# EMI_Probe.net
KiCad netlist of a schematic drawn in Altium Designer
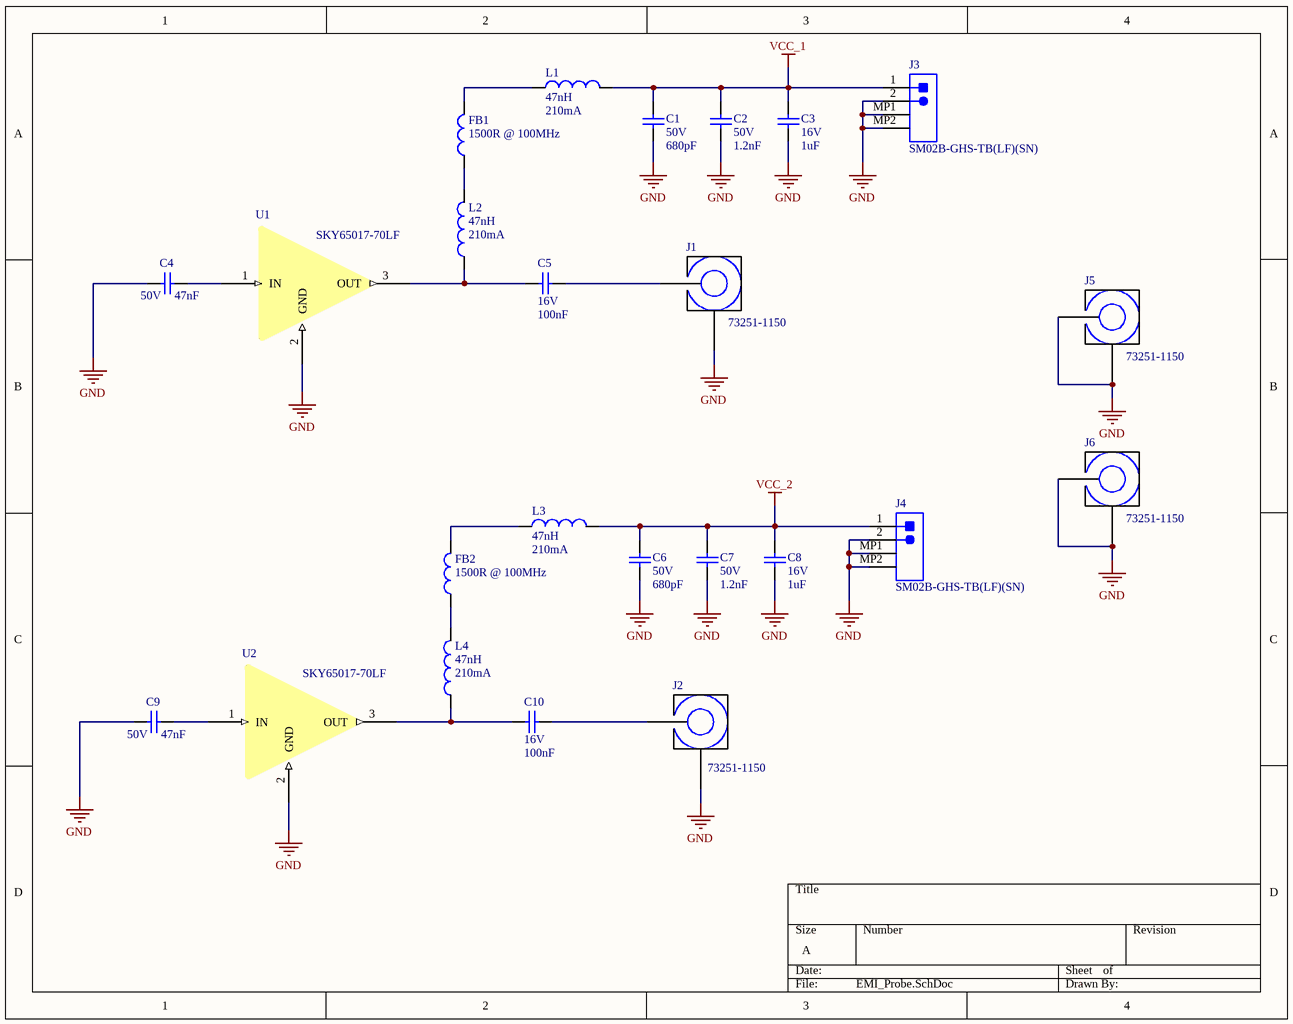
[diagram p0: EMI_Probe.SchDoc]

(export (version "E")
  (design (tool "Eeschema 10.0.6"))
  (components
    (comp (ref "C1")
      (value "680pF")
      (footprint "C0402[1005]")
      (description "680pF 50V X7R 10% 0402")
      (fields
        (field (name "MANUFACTURER") "Yageo")
        (field (name "MANUFACTURER PART NUMBER") "CC0402KRX7R9BB681")
        (field (name "VOLTAGE") "50V")
      )
      (libsource (lib "Kickmaker Library") (part "C680pF 50V 0402"))
    )
    (comp (ref "C2")
      (value "1.2nF")
      (footprint "C0603[1608]")
      (description "1.2nF 50V C0G,NP0 5% 0603")
      (fields
        (field (name "MANUFACTURER") "Walsin")
        (field (name "MANUFACTURER PART NUMBER") "0603N122J500CT")
        (field (name "VOLTAGE") "50V")
      )
      (libsource (lib "Kickmaker Library") (part "C1.2nF 50V 0603"))
    )
    (comp (ref "C3")
      (value "1uF")
      (footprint "C0402[1005]")
      (description "1uF 16V X5R 10% 0402")
      (fields
        (field (name "MANUFACTURER") "Samsung Electro-Mechanics")
        (field (name "MANUFACTURER PART NUMBER") "CL05A105KO5NNNC")
        (field (name "VOLTAGE") "16V")
      )
      (libsource (lib "Kickmaker Library") (part "C1uF 16V 0402"))
    )
    (comp (ref "C4")
      (value "47nF")
      (footprint "C0402[1005]")
      (description "47nF 50V X7R 10% 0402")
      (fields
        (field (name "MANUFACTURER") "Yageo")
        (field (name "MANUFACTURER PART NUMBER") "CC0402KRX7R9BB473")
        (field (name "VOLTAGE") "50V")
      )
      (libsource (lib "Kickmaker Library") (part "C47nF 50V 0402"))
    )
    (comp (ref "C5")
      (value "100nF")
      (footprint "C0402[1005]")
      (description "100nF 16V X7R 10% 0402")
      (fields
        (field (name "MANUFACTURER") "Kemet")
        (field (name "MANUFACTURER PART NUMBER") "C0402C104K4RACTU")
        (field (name "VOLTAGE") "16V")
      )
      (libsource (lib "Kickmaker Library") (part "C100nF 16V 0402"))
    )
    (comp (ref "C6")
      (value "680pF")
      (footprint "C0402[1005]")
      (description "680pF 50V X7R 10% 0402")
      (fields
        (field (name "MANUFACTURER") "Yageo")
        (field (name "MANUFACTURER PART NUMBER") "CC0402KRX7R9BB681")
        (field (name "VOLTAGE") "50V")
      )
      (libsource (lib "Kickmaker Library") (part "C680pF 50V 0402"))
    )
    (comp (ref "C7")
      (value "1.2nF")
      (footprint "C0603[1608]")
      (description "1.2nF 50V C0G,NP0 5% 0603")
      (fields
        (field (name "MANUFACTURER") "Walsin")
        (field (name "MANUFACTURER PART NUMBER") "0603N122J500CT")
        (field (name "VOLTAGE") "50V")
      )
      (libsource (lib "Kickmaker Library") (part "C1.2nF 50V 0603"))
    )
    (comp (ref "C8")
      (value "1uF")
      (footprint "C0402[1005]")
      (description "1uF 16V X5R 10% 0402")
      (fields
        (field (name "MANUFACTURER") "Samsung Electro-Mechanics")
        (field (name "MANUFACTURER PART NUMBER") "CL05A105KO5NNNC")
        (field (name "VOLTAGE") "16V")
      )
      (libsource (lib "Kickmaker Library") (part "C1uF 16V 0402"))
    )
    (comp (ref "C9")
      (value "47nF")
      (footprint "C0402[1005]")
      (description "47nF 50V X7R 10% 0402")
      (fields
        (field (name "MANUFACTURER") "Yageo")
        (field (name "MANUFACTURER PART NUMBER") "CC0402KRX7R9BB473")
        (field (name "VOLTAGE") "50V")
      )
      (libsource (lib "Kickmaker Library") (part "C47nF 50V 0402"))
    )
    (comp (ref "C10")
      (value "100nF")
      (footprint "C0402[1005]")
      (description "100nF 16V X7R 10% 0402")
      (fields
        (field (name "MANUFACTURER") "Kemet")
        (field (name "MANUFACTURER PART NUMBER") "C0402C104K4RACTU")
        (field (name "VOLTAGE") "16V")
      )
      (libsource (lib "Kickmaker Library") (part "C100nF 16V 0402"))
    )
    (comp (ref "FB1")
      (value "1500R @ 100MHz")
      (footprint "R0805[2012]")
      (description "1,5 kOhms @ 100MHz 1 Ligne de signal Ferrite Bead 0805 (2012 métrique) 1A 300mOhms")
      (fields
        (field (name "MANUFACTURER") "Wurth Electronics Inc.")
        (field (name "MANUFACTURER PART NUMBER") "742792097")
      )
      (libsource (lib "Kickmaker Library") (part "Ferrite bead 1.5 KOHM 0805 1LN"))
    )
    (comp (ref "FB2")
      (value "1500R @ 100MHz")
      (footprint "R0805[2012]")
      (description "1,5 kOhms @ 100MHz 1 Ligne de signal Ferrite Bead 0805 (2012 métrique) 1A 300mOhms")
      (fields
        (field (name "MANUFACTURER") "Wurth Electronics Inc.")
        (field (name "MANUFACTURER PART NUMBER") "742792097")
      )
      (libsource (lib "Kickmaker Library") (part "Ferrite bead 1.5 KOHM 0805 1LN"))
    )
    (comp (ref "J1")
      (value "73251-1150")
      (footprint "732511040")
      (fields (field (name "MANUFACTURER") "Molex"))
      (libsource (lib "Connector") (part "SMA RA 50ohm"))
    )
    (comp (ref "J2")
      (value "73251-1150")
      (footprint "732511040")
      (fields (field (name "MANUFACTURER") "Molex"))
      (libsource (lib "Connector") (part "SMA RA 50ohm"))
    )
    (comp (ref "J3")
      (value "SM02B-GHS-TB(LF)(SN)")
      (footprint "SM02B-GHS-TB")
      (description "Connector Header Surface Mount, Right Angle 2 position 0.049\" (1.25mm)")
      (fields (field (name "MANUFACTURER") "JST"))
      (libsource (lib "Kickmaker Library") (part "SM02B-GHS-TB(LF)(SN)"))
    )
    (comp (ref "J4")
      (value "SM02B-GHS-TB(LF)(SN)")
      (footprint "SM02B-GHS-TB")
      (description "Connector Header Surface Mount, Right Angle 2 position 0.049\" (1.25mm)")
      (fields (field (name "MANUFACTURER") "JST"))
      (libsource (lib "Kickmaker Library") (part "SM02B-GHS-TB(LF)(SN)"))
    )
    (comp (ref "J5")
      (value "73251-1150")
      (footprint "732511040")
      (fields (field (name "MANUFACTURER") "Molex"))
      (libsource (lib "Connector") (part "SMA RA 50ohm"))
    )
    (comp (ref "J6")
      (value "73251-1150")
      (footprint "732511040")
      (fields (field (name "MANUFACTURER") "Molex"))
      (libsource (lib "Connector") (part "SMA RA 50ohm"))
    )
    (comp (ref "L1")
      (value "47nH")
      (footprint "C0402[1005]")
      (description "47nH 210mA 5% 1Ohm")
      (fields
        (field (name "MANUFACTURER PART NUMBER") "LQW15AN47NJ00D")
        (field (name "MANUFACTURER") "Murata Electronics North America")
        (field (name "CURRENT RATING") "210mA")
      )
      (libsource (lib "Kickmaker Library") (part "L47nH 210mA 1Ohm 0402"))
    )
    (comp (ref "L2")
      (value "47nH")
      (footprint "C0402[1005]")
      (description "47nH 210mA 5% 1Ohm")
      (fields
        (field (name "MANUFACTURER PART NUMBER") "LQW15AN47NJ00D")
        (field (name "MANUFACTURER") "Murata Electronics North America")
        (field (name "CURRENT RATING") "210mA")
      )
      (libsource (lib "Kickmaker Library") (part "L47nH 210mA 1Ohm 0402"))
    )
    (comp (ref "L3")
      (value "47nH")
      (footprint "C0402[1005]")
      (description "47nH 210mA 5% 1Ohm")
      (fields
        (field (name "MANUFACTURER PART NUMBER") "LQW15AN47NJ00D")
        (field (name "MANUFACTURER") "Murata Electronics North America")
        (field (name "CURRENT RATING") "210mA")
      )
      (libsource (lib "Kickmaker Library") (part "L47nH 210mA 1Ohm 0402"))
    )
    (comp (ref "L4")
      (value "47nH")
      (footprint "C0402[1005]")
      (description "47nH 210mA 5% 1Ohm")
      (fields
        (field (name "MANUFACTURER PART NUMBER") "LQW15AN47NJ00D")
        (field (name "MANUFACTURER") "Murata Electronics North America")
        (field (name "CURRENT RATING") "210mA")
      )
      (libsource (lib "Kickmaker Library") (part "L47nH 210mA 1Ohm 0402"))
    )
    (comp (ref "U1")
      (value "SKY65017-70LF")
      (footprint "SOT-89")
      (description "Amplificateur RF .1-6.0GHz InGaP HBT Sm Sig Gain 20dB")
      (fields (field (name "MANUFACTURER") "Skyworks"))
      (libsource (lib "IC - Other") (part "SKY65017-70LF"))
    )
    (comp (ref "U2")
      (value "SKY65017-70LF")
      (footprint "SOT-89")
      (description "Amplificateur RF .1-6.0GHz InGaP HBT Sm Sig Gain 20dB")
      (fields (field (name "MANUFACTURER") "Skyworks"))
      (libsource (lib "IC - Other") (part "SKY65017-70LF"))
    )
  )
  (nets
    (net (code "1") (name "GND") (class "Default")
      (node (ref "C1") (pin "1") (pinfunction "1_1") (pintype "passive"))
      (node (ref "C2") (pin "1") (pinfunction "1_1") (pintype "passive"))
      (node (ref "C3") (pin "1") (pinfunction "1_1") (pintype "passive"))
      (node (ref "C4") (pin "2") (pinfunction "2_2") (pintype "passive"))
      (node (ref "C6") (pin "1") (pinfunction "1_1") (pintype "passive"))
      (node (ref "C7") (pin "1") (pinfunction "1_1") (pintype "passive"))
      (node (ref "C8") (pin "1") (pinfunction "1_1") (pintype "passive"))
      (node (ref "C9") (pin "2") (pinfunction "2_2") (pintype "passive"))
      (node (ref "J1") (pin "2") (pinfunction "2_2") (pintype "passive"))
      (node (ref "J2") (pin "2") (pinfunction "2_2") (pintype "passive"))
      (node (ref "J3") (pin "2") (pinfunction "2_2") (pintype "passive"))
      (node (ref "J3") (pin "MP1") (pinfunction "MP1_MP1") (pintype "passive"))
      (node (ref "J3") (pin "MP2") (pinfunction "MP2_MP2") (pintype "passive"))
      (node (ref "J4") (pin "2") (pinfunction "2_2") (pintype "passive"))
      (node (ref "J4") (pin "MP1") (pinfunction "MP1_MP1") (pintype "passive"))
      (node (ref "J4") (pin "MP2") (pinfunction "MP2_MP2") (pintype "passive"))
      (node (ref "J5") (pin "1") (pinfunction "1_1") (pintype "passive"))
      (node (ref "J5") (pin "2") (pinfunction "2_2") (pintype "passive"))
      (node (ref "J6") (pin "1") (pinfunction "1_1") (pintype "passive"))
      (node (ref "J6") (pin "2") (pinfunction "2_2") (pintype "passive"))
      (node (ref "U1") (pin "2") (pinfunction "GND_2") (pintype "input"))
      (node (ref "U2") (pin "2") (pinfunction "GND_2") (pintype "input"))
    )
    (net (code "2") (name "Net-(C5-Pad1)") (class "Default")
      (node (ref "C5") (pin "1") (pinfunction "1_1") (pintype "passive"))
      (node (ref "J1") (pin "1") (pinfunction "1_1") (pintype "passive"))
    )
    (net (code "3") (name "Net-(C10-Pad1)") (class "Default")
      (node (ref "C10") (pin "1") (pinfunction "1_1") (pintype "passive"))
      (node (ref "J2") (pin "1") (pinfunction "1_1") (pintype "passive"))
    )
    (net (code "4") (name "Net-(FB1-Pad1)") (class "Default")
      (node (ref "FB1") (pin "1") (pinfunction "1_1") (pintype "passive"))
      (node (ref "L2") (pin "2") (pinfunction "2_2") (pintype "passive"))
    )
    (net (code "5") (name "Net-(FB1-Pad2)") (class "Default")
      (node (ref "FB1") (pin "2") (pinfunction "2_2") (pintype "passive"))
      (node (ref "L1") (pin "1") (pinfunction "1_1") (pintype "passive"))
    )
    (net (code "6") (name "Net-(FB2-Pad1)") (class "Default")
      (node (ref "FB2") (pin "1") (pinfunction "1_1") (pintype "passive"))
      (node (ref "L4") (pin "2") (pinfunction "2_2") (pintype "passive"))
    )
    (net (code "7") (name "Net-(FB2-Pad2)") (class "Default")
      (node (ref "FB2") (pin "2") (pinfunction "2_2") (pintype "passive"))
      (node (ref "L3") (pin "1") (pinfunction "1_1") (pintype "passive"))
    )
    (net (code "8") (name "Net-(U1-IN)") (class "Default")
      (node (ref "C4") (pin "1") (pinfunction "1_1") (pintype "passive"))
      (node (ref "U1") (pin "1") (pinfunction "IN_1") (pintype "input"))
    )
    (net (code "9") (name "Net-(U1-OUT)") (class "Default")
      (node (ref "C5") (pin "2") (pinfunction "2_2") (pintype "passive"))
      (node (ref "L2") (pin "1") (pinfunction "1_1") (pintype "passive"))
      (node (ref "U1") (pin "3") (pinfunction "OUT_3") (pintype "output"))
    )
    (net (code "10") (name "Net-(U2-IN)") (class "Default")
      (node (ref "C9") (pin "1") (pinfunction "1_1") (pintype "passive"))
      (node (ref "U2") (pin "1") (pinfunction "IN_1") (pintype "input"))
    )
    (net (code "11") (name "Net-(U2-OUT)") (class "Default")
      (node (ref "C10") (pin "2") (pinfunction "2_2") (pintype "passive"))
      (node (ref "L4") (pin "1") (pinfunction "1_1") (pintype "passive"))
      (node (ref "U2") (pin "3") (pinfunction "OUT_3") (pintype "output"))
    )
    (net (code "12") (name "VCC_1") (class "Default")
      (node (ref "C1") (pin "2") (pinfunction "2_2") (pintype "passive"))
      (node (ref "C2") (pin "2") (pinfunction "2_2") (pintype "passive"))
      (node (ref "C3") (pin "2") (pinfunction "2_2") (pintype "passive"))
      (node (ref "J3") (pin "1") (pinfunction "1_1") (pintype "passive"))
      (node (ref "L1") (pin "2") (pinfunction "2_2") (pintype "passive"))
    )
    (net (code "13") (name "VCC_2") (class "Default")
      (node (ref "C6") (pin "2") (pinfunction "2_2") (pintype "passive"))
      (node (ref "C7") (pin "2") (pinfunction "2_2") (pintype "passive"))
      (node (ref "C8") (pin "2") (pinfunction "2_2") (pintype "passive"))
      (node (ref "J4") (pin "1") (pinfunction "1_1") (pintype "passive"))
      (node (ref "L3") (pin "2") (pinfunction "2_2") (pintype "passive"))
    )
  )
)
